# 30-FT4232_LEVEL_TRANSLATOR.net
KiCad netlist of a schematic drawn in Altium Designer
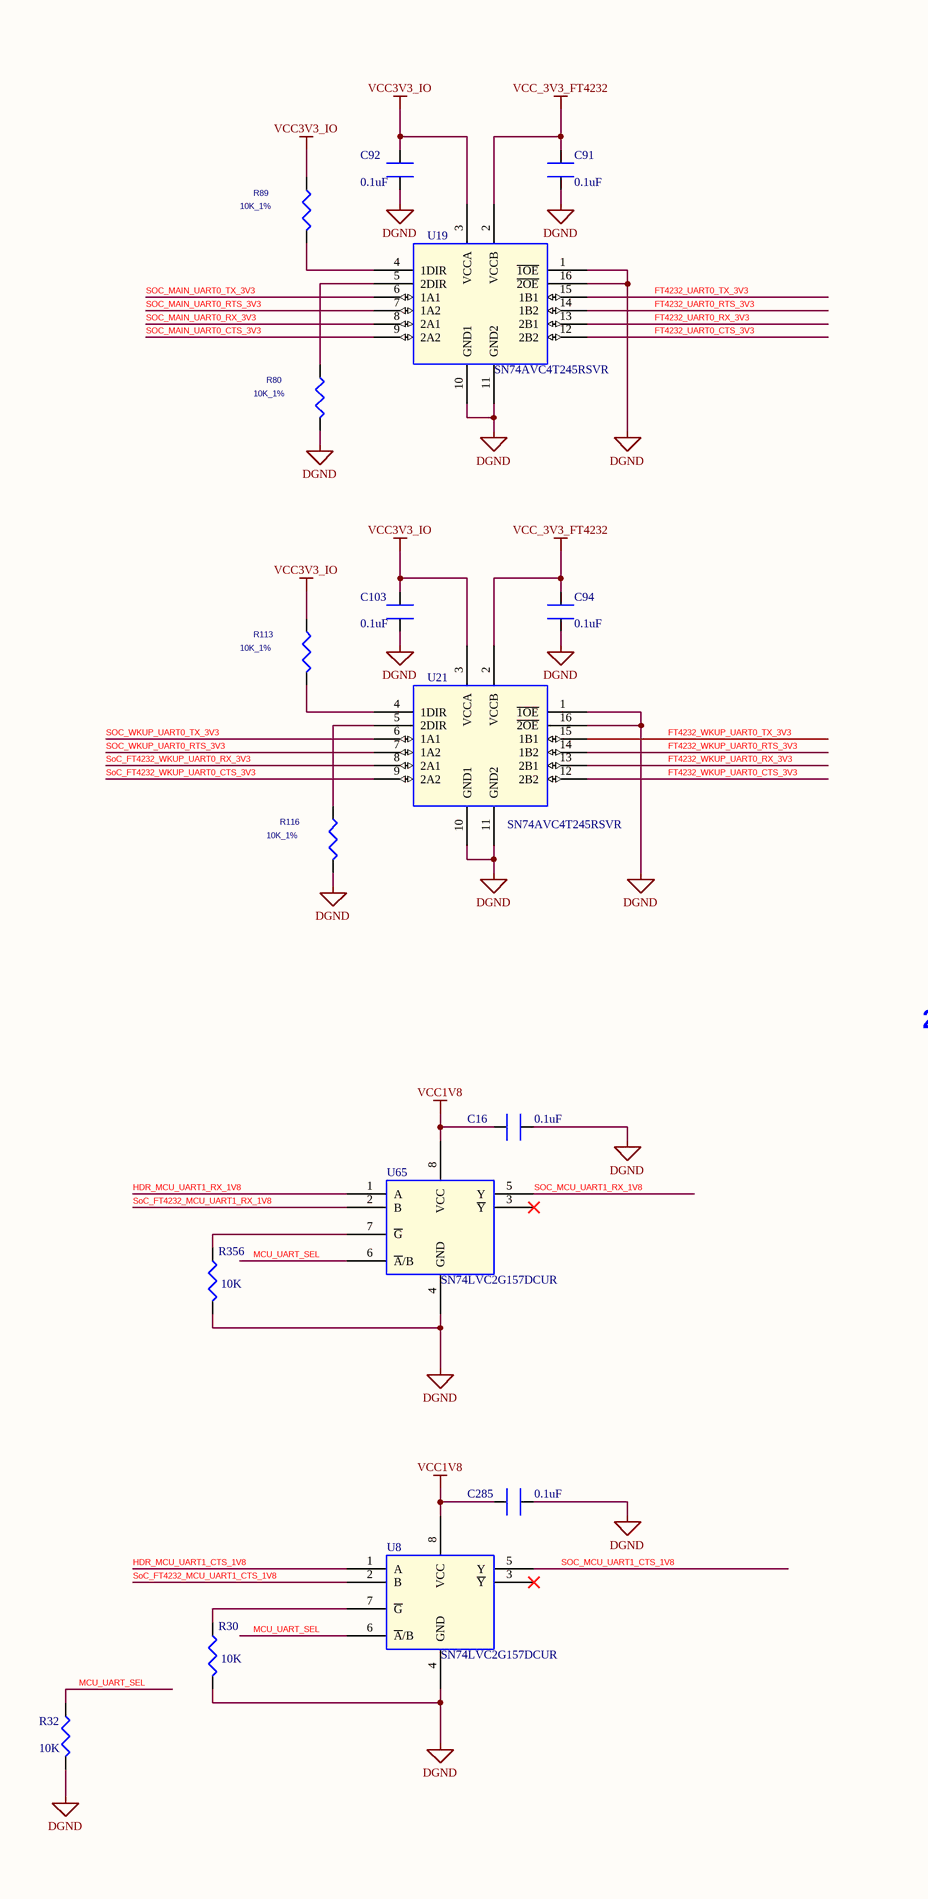
[diagram p0: 30-FT4232 LEVEL TRANSLATOR.SchDoc, left]
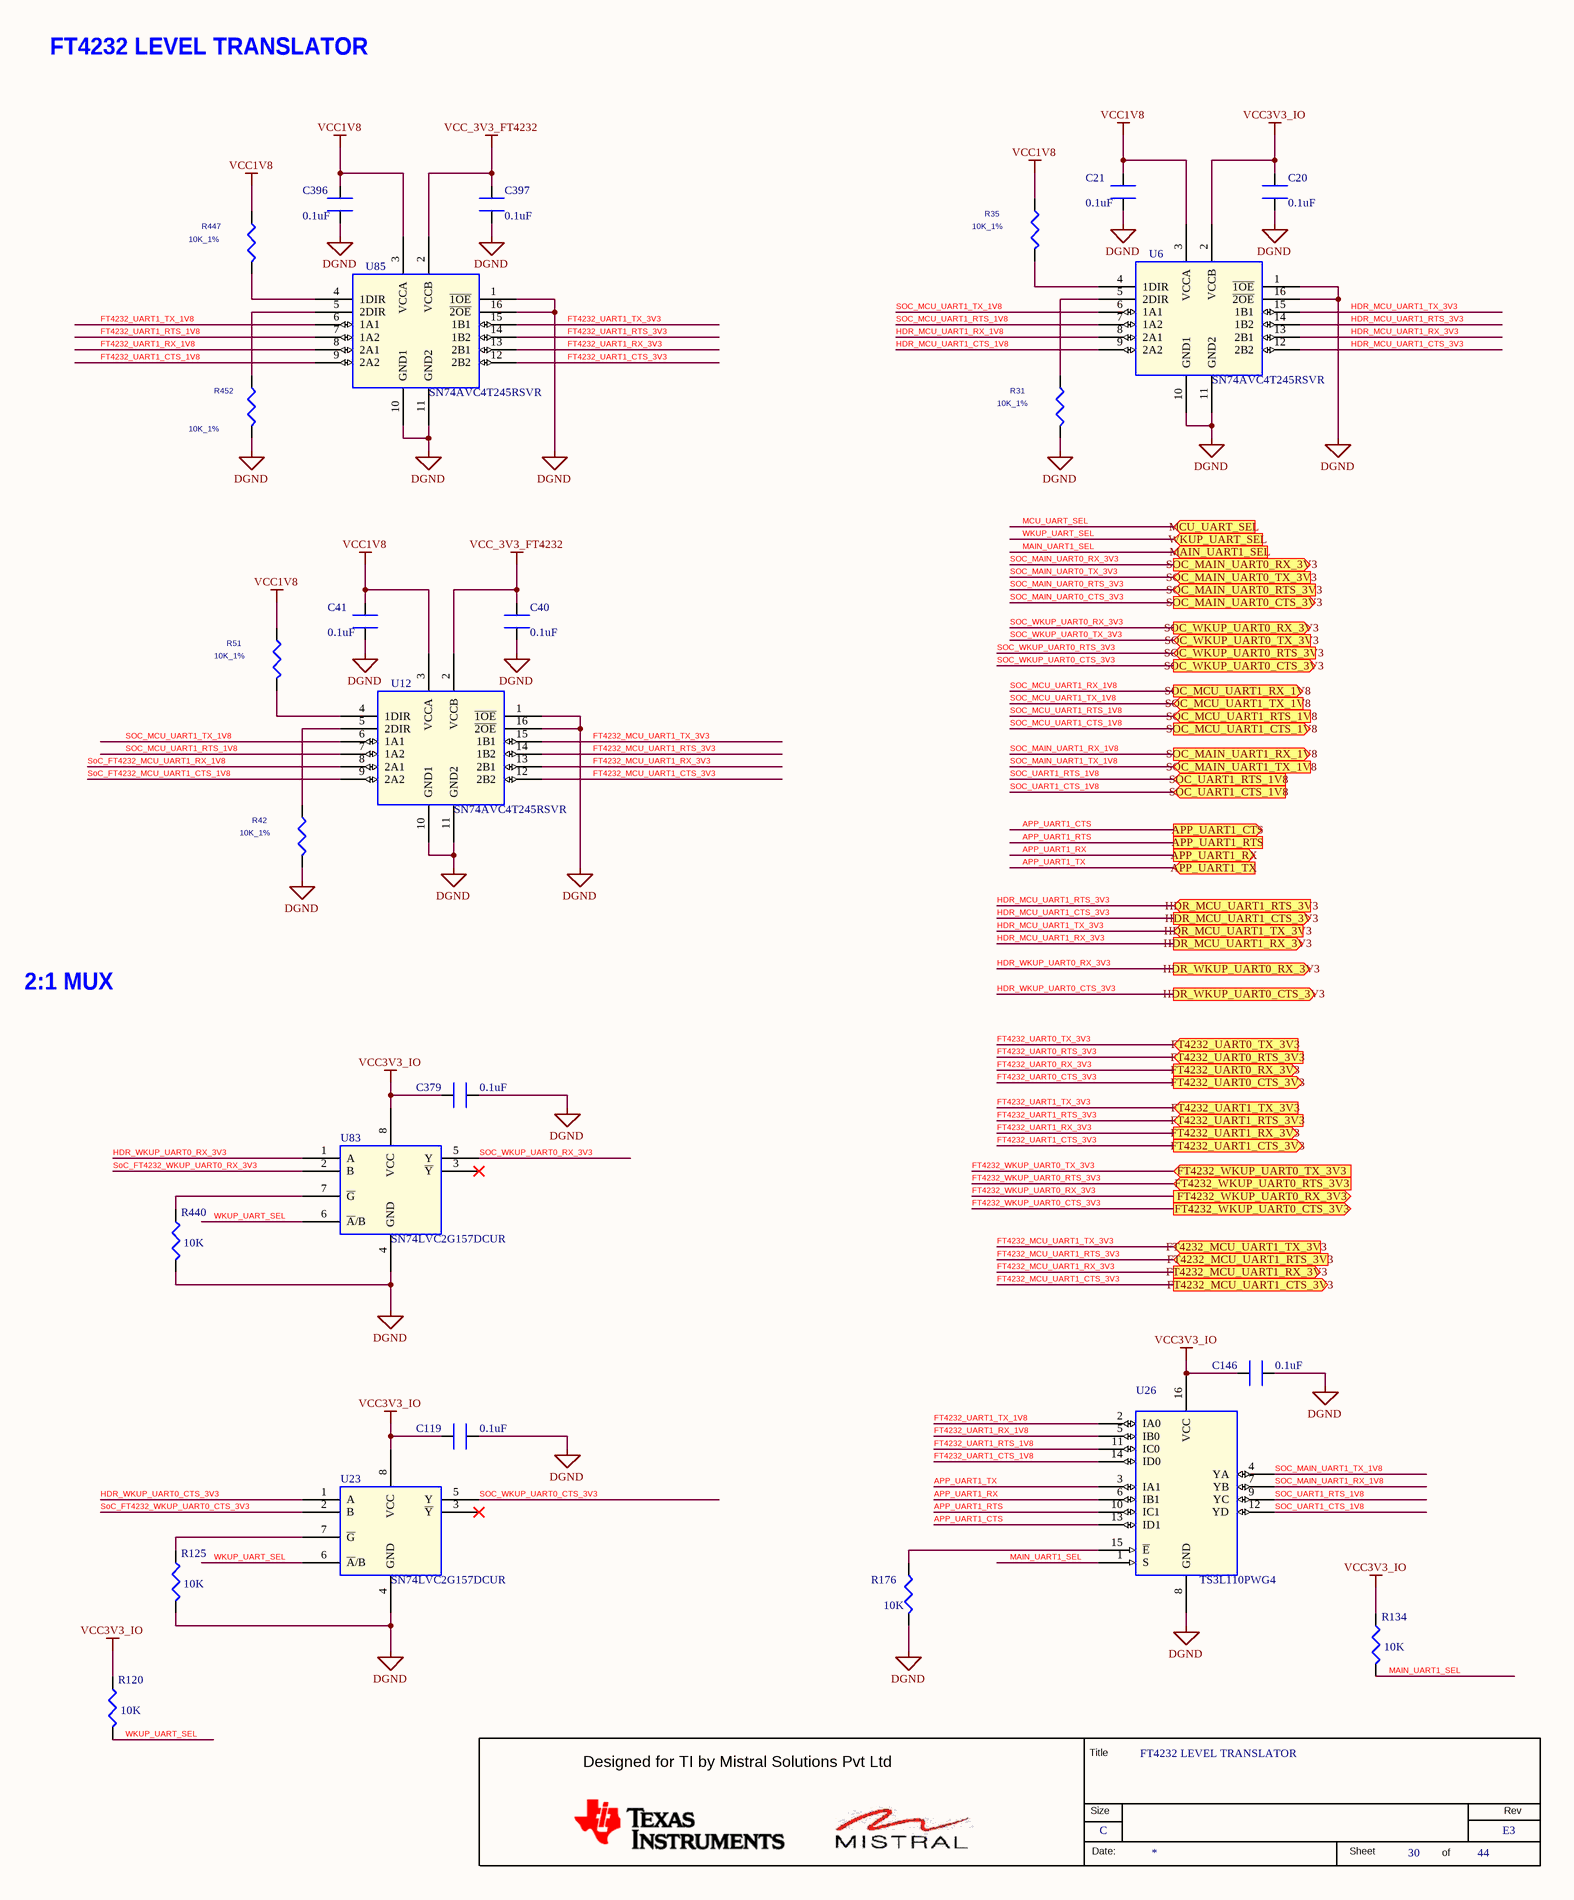
[diagram p1: 30-FT4232 LEVEL TRANSLATOR.SchDoc, right]

(export (version "E")
  (design (tool "Eeschema 10.0.6"))
  (components
    (comp (ref "C16")
      (value "0.1uF")
      (footprint "TMDX654GPEVM_BRD:CAP0201_0-5")
      (description "CAP CERAMIC 0.1uF 16V 10% X5R 0201")
      (fields
        (field (name "MISTRAL PART NO") "120009030072-R")
        (field (name "MFR_PART_NUMBER") "GRM033R61C104KE84J")
      )
      (libsource (lib "*") (part "CAP_Dup3"))
    )
    (comp (ref "C20")
      (value "0.1uF")
      (footprint "TMDX654GPEVM_BRD:CAP0201_0-5")
      (description "CAP CERAMIC 0.1uF 16V 10% X5R 0201")
      (fields (field (name "DISTRIBUTOR_PART_NUMBER") "490-16742-1-ND") (field (name "VOLTAGE") "16V"))
      (libsource (lib "*") (part "CAP_Dup3"))
    )
    (comp (ref "C21")
      (value "0.1uF")
      (footprint "TMDX654GPEVM_BRD:CAP0201_0-5")
      (description "CAP CERAMIC 0.1uF 16V 10% X5R 0201")
      (fields
        (field (name "MISTRAL PART NO") "120009030072-R")
        (field (name "MFR_PART_NUMBER") "GRM033R61C104KE84J")
      )
      (libsource (lib "*") (part "CAP_Dup3"))
    )
    (comp (ref "C40")
      (value "0.1uF")
      (footprint "TMDX654GPEVM_BRD:CAP0201_0-5")
      (description "CAP CERAMIC 0.1uF 16V 10% X5R 0201")
      (fields (field (name "DISTRIBUTOR_PART_NUMBER") "490-16742-1-ND") (field (name "VOLTAGE") "16V"))
      (libsource (lib "*") (part "CAP_Dup3"))
    )
    (comp (ref "C41")
      (value "0.1uF")
      (footprint "TMDX654GPEVM_BRD:CAP0201_0-5")
      (description "CAP CERAMIC 0.1uF 16V 10% X5R 0201")
      (fields
        (field (name "MISTRAL PART NO") "120009030072-R")
        (field (name "MFR_PART_NUMBER") "GRM033R61C104KE84J")
      )
      (libsource (lib "*") (part "CAP_Dup3"))
    )
    (comp (ref "C91")
      (value "0.1uF")
      (footprint "TMDX654GPEVM_BRD:CAP0201_0-5")
      (description "CAP CERAMIC 0.1uF 16V 10% X5R 0201")
      (fields
        (field (name "MISTRAL PART NO") "120009030072-R")
        (field (name "MFR_PART_NUMBER") "GRM033R61C104KE84J")
      )
      (libsource (lib "*") (part "CAP_Dup3"))
    )
    (comp (ref "C92")
      (value "0.1uF")
      (footprint "TMDX654GPEVM_BRD:CAP0201_0-5")
      (description "CAP CERAMIC 0.1uF 16V 10% X5R 0201")
      (fields (field (name "DISTRIBUTOR_PART_NUMBER") "490-16742-1-ND") (field (name "VOLTAGE") "16V"))
      (libsource (lib "*") (part "CAP_Dup3"))
    )
    (comp (ref "C94")
      (value "0.1uF")
      (footprint "TMDX654GPEVM_BRD:CAP0201_0-5")
      (description "CAP CERAMIC 0.1uF 16V 10% X5R 0201")
      (fields
        (field (name "MISTRAL PART NO") "120009030072-R")
        (field (name "MFR_PART_NUMBER") "GRM033R61C104KE84J")
      )
      (libsource (lib "*") (part "CAP_Dup3"))
    )
    (comp (ref "C103")
      (value "0.1uF")
      (footprint "TMDX654GPEVM_BRD:CAP0201_0-5")
      (description "CAP CERAMIC 0.1uF 16V 10% X5R 0201")
      (fields (field (name "DISTRIBUTOR_PART_NUMBER") "490-16742-1-ND") (field (name "VOLTAGE") "16V"))
      (libsource (lib "*") (part "CAP_Dup3"))
    )
    (comp (ref "C119")
      (value "0.1uF")
      (footprint "TMDX654GPEVM_BRD:CAP0201_0-5")
      (description "CAP CERAMIC 0.1uF 16V 10% X5R 0201")
      (fields (field (name "DISTRIBUTOR_PART_NUMBER") "490-16742-1-ND") (field (name "VOLTAGE") "16V"))
      (libsource (lib "*") (part "CAP_Dup3"))
    )
    (comp (ref "C146")
      (value "0.1uF")
      (footprint "TMDX654GPEVM_BRD:CAP0201_0-5")
      (description "CAP CERAMIC 0.1uF 16V 10% X5R 0201")
      (fields
        (field (name "MISTRAL PART NO") "120009030072-R")
        (field (name "MFR_PART_NUMBER") "GRM033R61C104KE84J")
      )
      (libsource (lib "*") (part "CAP_Dup3"))
    )
    (comp (ref "C285")
      (value "0.1uF")
      (footprint "TMDX654GPEVM_BRD:CAP0201_0-5")
      (description "CAP CERAMIC 0.1uF 16V 10% X5R 0201")
      (fields (field (name "DISTRIBUTOR_PART_NUMBER") "490-16742-1-ND") (field (name "VOLTAGE") "16V"))
      (libsource (lib "*") (part "CAP_Dup3"))
    )
    (comp (ref "C379")
      (value "0.1uF")
      (footprint "TMDX654GPEVM_BRD:CAP0201_0-5")
      (description "CAP CERAMIC 0.1uF 16V 10% X5R 0201")
      (fields
        (field (name "MISTRAL PART NO") "120009030072-R")
        (field (name "MFR_PART_NUMBER") "GRM033R61C104KE84J")
      )
      (libsource (lib "*") (part "CAP_Dup3"))
    )
    (comp (ref "C396")
      (value "0.1uF")
      (footprint "TMDX654GPEVM_BRD:CAP0201_0-5")
      (description "CAP CERAMIC 0.1uF 16V 10% X5R 0201")
      (fields (field (name "DISTRIBUTOR_PART_NUMBER") "490-16742-1-ND") (field (name "VOLTAGE") "16V"))
      (libsource (lib "*") (part "CAP_Dup3"))
    )
    (comp (ref "C397")
      (value "0.1uF")
      (footprint "TMDX654GPEVM_BRD:CAP0201_0-5")
      (description "CAP CERAMIC 0.1uF 16V 10% X5R 0201")
      (fields
        (field (name "MISTRAL PART NO") "120009030072-R")
        (field (name "MFR_PART_NUMBER") "GRM033R61C104KE84J")
      )
      (libsource (lib "*") (part "CAP_Dup3"))
    )
    (comp (ref "R30")
      (value "10K")
      (footprint "RES0402_0-5")
      (description "RES 10K 1/16W 5% 0402")
      (fields
        (field (name "MISTRAL PART NO") "110009030208-R")
        (field (name "MFR_PART_NUMBER") "RC0402JR-0710KL")
      )
      (libsource (lib "*") (part "RESISTOR_Dup5"))
    )
    (comp (ref "R31")
      (value "10K_1%")
      (footprint "RES0402_0-5")
      (description "RES 10K 1/16W 1% 0402")
      (fields (field (name "DISTRIBUTOR_PART_NUMBER") "311-10.0KLRTR-ND") (field (name "TOLERANCE") "1%"))
      (libsource (lib "*") (part "RESISTOR_Dup2"))
    )
    (comp (ref "R32")
      (value "10K")
      (footprint "RES0402_0-5")
      (description "RES 10K 1/16W 5% 0402")
      (fields
        (field (name "MISTRAL PART NO") "110009030208-R")
        (field (name "MFR_PART_NUMBER") "RC0402JR-0710KL")
      )
      (libsource (lib "*") (part "RESISTOR_Dup5"))
    )
    (comp (ref "R35")
      (value "10K_1%")
      (footprint "RES0402_0-5")
      (description "RES 10K 1/16W 1% 0402")
      (fields (field (name "DISTRIBUTOR_PART_NUMBER") "311-10.0KLRTR-ND") (field (name "TOLERANCE") "1%"))
      (libsource (lib "*") (part "RESISTOR_Dup2"))
    )
    (comp (ref "R42")
      (value "10K_1%")
      (footprint "RES0402_0-5")
      (description "RES 10K 1/16W 1% 0402")
      (fields (field (name "VOLTAGE") "NA") (field (name "DISTRIBUTOR_PART_NUMBER") "311-10.0KLRTR-ND"))
      (libsource (lib "*") (part "RESISTOR_Dup2"))
    )
    (comp (ref "R51")
      (value "10K_1%")
      (footprint "RES0402_0-5")
      (description "RES 10K 1/16W 1% 0402")
      (fields (field (name "VOLTAGE") "NA") (field (name "DISTRIBUTOR_PART_NUMBER") "311-10.0KLRTR-ND"))
      (libsource (lib "*") (part "RESISTOR_Dup2"))
    )
    (comp (ref "R80")
      (value "10K_1%")
      (footprint "RES0402_0-5")
      (description "RES 10K 1/16W 1% 0402")
      (fields (field (name "VOLTAGE") "NA") (field (name "DISTRIBUTOR_PART_NUMBER") "311-10.0KLRTR-ND"))
      (libsource (lib "*") (part "RESISTOR_Dup2"))
    )
    (comp (ref "R89")
      (value "10K_1%")
      (footprint "RES0402_0-5")
      (description "RES 10K 1/16W 1% 0402")
      (fields (field (name "VOLTAGE") "NA") (field (name "MISTRAL PART NO") "110009030220-P"))
      (libsource (lib "*") (part "RESISTOR_Dup2"))
    )
    (comp (ref "R113")
      (value "10K_1%")
      (footprint "RES0402_0-5")
      (description "RES 10K 1/16W 1% 0402")
      (fields (field (name "VOLTAGE") "NA") (field (name "MISTRAL PART NO") "110009030220-P"))
      (libsource (lib "*") (part "RESISTOR_Dup2"))
    )
    (comp (ref "R116")
      (value "10K_1%")
      (footprint "RES0402_0-5")
      (description "RES 10K 1/16W 1% 0402")
      (fields (field (name "VOLTAGE") "NA") (field (name "MISTRAL PART NO") "110009030220-P"))
      (libsource (lib "*") (part "RESISTOR_Dup2"))
    )
    (comp (ref "R120")
      (value "10K")
      (footprint "RES0402_0-5")
      (description "RES 10K 1/16W 5% 0402")
      (fields (field (name "DISTRIBUTOR_PART_NUMBER") "311-10KJRCT-ND") (field (name "VOLTAGE") "NA"))
      (libsource (lib "*") (part "RESISTOR_Dup5"))
    )
    (comp (ref "R125")
      (value "10K")
      (footprint "RES0402_0-5")
      (description "RES 10K 1/16W 5% 0402")
      (fields
        (field (name "MISTRAL PART NO") "110009030208-R")
        (field (name "MFR_PART_NUMBER") "RC0402JR-0710KL")
      )
      (libsource (lib "*") (part "RESISTOR_Dup5"))
    )
    (comp (ref "R134")
      (value "10K")
      (footprint "RES0402_0-5")
      (description "RES 10K 1/16W 5% 0402")
      (fields
        (field (name "MISTRAL PART NO") "110009030208-R")
        (field (name "MFR_PART_NUMBER") "RC0402JR-0710KL")
      )
      (libsource (lib "*") (part "RESISTOR_Dup5"))
    )
    (comp (ref "R176")
      (value "10K")
      (footprint "RES0402_0-5")
      (description "RES 10K 1/16W 5% 0402")
      (fields (field (name "DISTRIBUTOR_PART_NUMBER") "311-10KJRCT-ND") (field (name "VOLTAGE") "NA"))
      (libsource (lib "*") (part "RESISTOR_Dup5"))
    )
    (comp (ref "R356")
      (value "10K")
      (footprint "RES0402_0-5")
      (description "RES 10K 1/16W 5% 0402")
      (fields (field (name "DISTRIBUTOR_PART_NUMBER") "311-10KJRCT-ND") (field (name "VOLTAGE") "NA"))
      (libsource (lib "*") (part "RESISTOR_Dup5"))
    )
    (comp (ref "R440")
      (value "10K")
      (footprint "RES0402_0-5")
      (description "RES 10K 1/16W 5% 0402")
      (fields (field (name "DISTRIBUTOR_PART_NUMBER") "311-10KJRCT-ND") (field (name "VOLTAGE") "NA"))
      (libsource (lib "*") (part "RESISTOR_Dup5"))
    )
    (comp (ref "R447")
      (value "10K_1%")
      (footprint "RES0402_0-5")
      (description "RES 10K 1/16W 1% 0402")
      (fields (field (name "VOLTAGE") "NA") (field (name "MISTRAL PART NO") "110009030220-P"))
      (libsource (lib "*") (part "RESISTOR_Dup2"))
    )
    (comp (ref "R452")
      (value "10K_1%")
      (footprint "RES0402_0-5")
      (description "RES 10K 1/16W 1% 0402")
      (fields (field (name "DISTRIBUTOR_PART_NUMBER") "311-10.0KLRTR-ND") (field (name "TOLERANCE") "1%"))
      (libsource (lib "*") (part "RESISTOR_Dup2"))
    )
    (comp (ref "U6")
      (value "SN74AVC4T245RSVR")
      (footprint "UQFN16_15-74_105X75_0-6")
      (description "IC BUS TRANSCEIVER 4-BIT DUAL SUPPLY QFN16")
      (fields (field (name "MISTRAL PART NO") "141011040011-R") (field (name "TOLERANCE") "NA"))
      (libsource (lib "*") (part "SN74AVC4T245RSV_UQFN16"))
    )
    (comp (ref "U8")
      (value "SN74LVC2G157DCUR")
      (footprint "VSSOP8_19-68_85X95_0-9")
      (description "IC 2-LINE TO 1-LINE DATA SELECTOR MULTIPLEXER VSSOP8")
      (fields (field (name "DISTRIBUTOR_PART_NUMBER") "296-12605-1-ND") (field (name "VOLTAGE") "NA"))
      (libsource (lib "*") (part "SN74LVC2G157DCUR_VSSOP8"))
    )
    (comp (ref "U12")
      (value "SN74AVC4T245RSVR")
      (footprint "UQFN16_15-74_105X75_0-6")
      (description "IC BUS TRANSCEIVER 4-BIT DUAL SUPPLY QFN16")
      (fields (field (name "MISTRAL PART NO") "141011040011-R") (field (name "TOLERANCE") "NA"))
      (libsource (lib "*") (part "SN74AVC4T245RSV_UQFN16"))
    )
    (comp (ref "U19")
      (value "SN74AVC4T245RSVR")
      (footprint "UQFN16_15-74_105X75_0-6")
      (description "IC BUS TRANSCEIVER 4-BIT DUAL SUPPLY QFN16")
      (fields (field (name "DISTRIBUTOR_PART_NUMBER") "296-24366-1-ND") (field (name "VOLTAGE") "NA"))
      (libsource (lib "*") (part "SN74AVC4T245RSV_UQFN16"))
    )
    (comp (ref "U21")
      (value "SN74AVC4T245RSVR")
      (footprint "UQFN16_15-74_105X75_0-6")
      (description "IC BUS TRANSCEIVER 4-BIT DUAL SUPPLY QFN16")
      (fields (field (name "MISTRAL PART NO") "141011040011-R") (field (name "TOLERANCE") "NA"))
      (libsource (lib "*") (part "SN74AVC4T245RSV_UQFN16"))
    )
    (comp (ref "U23")
      (value "SN74LVC2G157DCUR")
      (footprint "VSSOP8_19-68_85X95_0-9")
      (description "IC 2-LINE TO 1-LINE DATA SELECTOR MULTIPLEXER VSSOP8")
      (fields (field (name "MISTRAL PART NO") "141017090014-R") (field (name "TOLERANCE") "NA"))
      (libsource (lib "*") (part "SN74LVC2G157DCUR_VSSOP8"))
    )
    (comp (ref "U26")
      (value "TS3L110PWG4")
      (footprint "TSSOP16_25-59_205X180")
      (description "IC QUAD SPDT SWITCH 8-4 CHANNEL MULTIPLEXER/DEMULTIPLEXER TSSOP16")
      (fields (field (name "MISTRAL PART NO") "140114110002-R") (field (name "TOLERANCE") "NA"))
      (libsource (lib "*") (part "TS3L110PWG4_TSSOP16"))
    )
    (comp (ref "U65")
      (value "SN74LVC2G157DCUR")
      (footprint "VSSOP8_19-68_85X95_0-9")
      (description "IC 2-LINE TO 1-LINE DATA SELECTOR MULTIPLEXER VSSOP8")
      (fields (field (name "MISTRAL PART NO") "141017090014-R") (field (name "TOLERANCE") "NA"))
      (libsource (lib "*") (part "SN74LVC2G157DCUR_VSSOP8"))
    )
    (comp (ref "U83")
      (value "SN74LVC2G157DCUR")
      (footprint "VSSOP8_19-68_85X95_0-9")
      (description "IC 2-LINE TO 1-LINE DATA SELECTOR MULTIPLEXER VSSOP8")
      (fields (field (name "DISTRIBUTOR_PART_NUMBER") "296-12605-1-ND") (field (name "VOLTAGE") "NA"))
      (libsource (lib "*") (part "SN74LVC2G157DCUR_VSSOP8"))
    )
    (comp (ref "U85")
      (value "SN74AVC4T245RSVR")
      (footprint "UQFN16_15-74_105X75_0-6")
      (description "IC BUS TRANSCEIVER 4-BIT DUAL SUPPLY QFN16")
      (fields (field (name "DISTRIBUTOR_PART_NUMBER") "296-24366-1-ND") (field (name "VOLTAGE") "NA"))
      (libsource (lib "*") (part "SN74AVC4T245RSV_UQFN16"))
    )
  )
  (nets
    (net (code "1") (name "/APP_UART1_CTS") (class "Default")
      (node (ref "U26") (pin "13") (pinfunction "ID1_13") (pintype "bidirectional"))
    )
    (net (code "2") (name "/APP_UART1_RTS") (class "Default")
      (node (ref "U26") (pin "10") (pinfunction "IC1_10") (pintype "bidirectional"))
    )
    (net (code "3") (name "/APP_UART1_RX") (class "Default")
      (node (ref "U26") (pin "6") (pinfunction "IB1_6") (pintype "bidirectional"))
    )
    (net (code "4") (name "/APP_UART1_TX") (class "Default")
      (node (ref "U26") (pin "3") (pinfunction "IA1_3") (pintype "bidirectional"))
    )
    (net (code "5") (name "/FT4232_MCU_UART1_CTS_3V3") (class "Default")
      (node (ref "U12") (pin "12") (pinfunction "2B2_12") (pintype "bidirectional"))
    )
    (net (code "6") (name "/FT4232_MCU_UART1_RTS_3V3") (class "Default")
      (node (ref "U12") (pin "14") (pinfunction "1B2_14") (pintype "bidirectional"))
    )
    (net (code "7") (name "/FT4232_MCU_UART1_RX_3V3") (class "Default")
      (node (ref "U12") (pin "13") (pinfunction "2B1_13") (pintype "bidirectional"))
    )
    (net (code "8") (name "/FT4232_MCU_UART1_TX_3V3") (class "Default")
      (node (ref "U12") (pin "15") (pinfunction "1B1_15") (pintype "bidirectional"))
    )
    (net (code "9") (name "/FT4232_UART0_CTS_3V3") (class "Default")
      (node (ref "U19") (pin "12") (pinfunction "2B2_12") (pintype "bidirectional"))
    )
    (net (code "10") (name "/FT4232_UART0_RTS_3V3") (class "Default")
      (node (ref "U19") (pin "14") (pinfunction "1B2_14") (pintype "bidirectional"))
    )
    (net (code "11") (name "/FT4232_UART0_RX_3V3") (class "Default")
      (node (ref "U19") (pin "13") (pinfunction "2B1_13") (pintype "bidirectional"))
    )
    (net (code "12") (name "/FT4232_UART0_TX_3V3") (class "Default")
      (node (ref "U19") (pin "15") (pinfunction "1B1_15") (pintype "bidirectional"))
    )
    (net (code "13") (name "/FT4232_UART1_CTS_1V8") (class "Default")
      (node (ref "U26") (pin "14") (pinfunction "ID0_14") (pintype "bidirectional"))
      (node (ref "U85") (pin "9") (pinfunction "2A2_9") (pintype "bidirectional"))
    )
    (net (code "14") (name "/FT4232_UART1_CTS_3V3") (class "Default")
      (node (ref "U85") (pin "12") (pinfunction "2B2_12") (pintype "bidirectional"))
    )
    (net (code "15") (name "/FT4232_UART1_RTS_1V8") (class "Default")
      (node (ref "U26") (pin "11") (pinfunction "IC0_11") (pintype "bidirectional"))
      (node (ref "U85") (pin "7") (pinfunction "1A2_7") (pintype "bidirectional"))
    )
    (net (code "16") (name "/FT4232_UART1_RTS_3V3") (class "Default")
      (node (ref "U85") (pin "14") (pinfunction "1B2_14") (pintype "bidirectional"))
    )
    (net (code "17") (name "/FT4232_UART1_RX_1V8") (class "Default")
      (node (ref "U26") (pin "5") (pinfunction "IB0_5") (pintype "bidirectional"))
      (node (ref "U85") (pin "8") (pinfunction "2A1_8") (pintype "bidirectional"))
    )
    (net (code "18") (name "/FT4232_UART1_RX_3V3") (class "Default")
      (node (ref "U85") (pin "13") (pinfunction "2B1_13") (pintype "bidirectional"))
    )
    (net (code "19") (name "/FT4232_UART1_TX_1V8") (class "Default")
      (node (ref "U26") (pin "2") (pinfunction "IA0_2") (pintype "bidirectional"))
      (node (ref "U85") (pin "6") (pinfunction "1A1_6") (pintype "bidirectional"))
    )
    (net (code "20") (name "/FT4232_UART1_TX_3V3") (class "Default")
      (node (ref "U85") (pin "15") (pinfunction "1B1_15") (pintype "bidirectional"))
    )
    (net (code "21") (name "/FT4232_WKUP_UART0_CTS_3V3") (class "Default")
      (node (ref "U21") (pin "12") (pinfunction "2B2_12") (pintype "bidirectional"))
    )
    (net (code "22") (name "/FT4232_WKUP_UART0_RTS_3V3") (class "Default")
      (node (ref "U21") (pin "14") (pinfunction "1B2_14") (pintype "bidirectional"))
    )
    (net (code "23") (name "/FT4232_WKUP_UART0_RX_3V3") (class "Default")
      (node (ref "U21") (pin "13") (pinfunction "2B1_13") (pintype "bidirectional"))
    )
    (net (code "24") (name "/FT4232_WKUP_UART0_TX_3V3") (class "Default")
      (node (ref "U21") (pin "15") (pinfunction "1B1_15") (pintype "bidirectional"))
    )
    (net (code "25") (name "/HDR_MCU_UART1_CTS_1V8") (class "Default")
      (node (ref "U6") (pin "9") (pinfunction "2A2_9") (pintype "bidirectional"))
      (node (ref "U8") (pin "1") (pinfunction "A_1") (pintype "passive"))
    )
    (net (code "26") (name "/HDR_MCU_UART1_CTS_3V3") (class "Default")
      (node (ref "U6") (pin "12") (pinfunction "2B2_12") (pintype "bidirectional"))
    )
    (net (code "27") (name "/HDR_MCU_UART1_RTS_3V3") (class "Default")
      (node (ref "U6") (pin "14") (pinfunction "1B2_14") (pintype "bidirectional"))
    )
    (net (code "28") (name "/HDR_MCU_UART1_RX_1V8") (class "Default")
      (node (ref "U6") (pin "8") (pinfunction "2A1_8") (pintype "bidirectional"))
      (node (ref "U65") (pin "1") (pinfunction "A_1") (pintype "passive"))
    )
    (net (code "29") (name "/HDR_MCU_UART1_RX_3V3") (class "Default")
      (node (ref "U6") (pin "13") (pinfunction "2B1_13") (pintype "bidirectional"))
    )
    (net (code "30") (name "/HDR_MCU_UART1_TX_3V3") (class "Default")
      (node (ref "U6") (pin "15") (pinfunction "1B1_15") (pintype "bidirectional"))
    )
    (net (code "31") (name "/HDR_WKUP_UART0_CTS_3V3") (class "Default")
      (node (ref "U23") (pin "1") (pinfunction "A_1") (pintype "passive"))
    )
    (net (code "32") (name "/HDR_WKUP_UART0_RX_3V3") (class "Default")
      (node (ref "U83") (pin "1") (pinfunction "A_1") (pintype "passive"))
    )
    (net (code "33") (name "/MAIN_UART1_SEL") (class "Default")
      (node (ref "R134") (pin "2") (pinfunction "2_2") (pintype "passive"))
      (node (ref "U26") (pin "1") (pinfunction "S_1") (pintype "input"))
    )
    (net (code "34") (name "/MCU_UART_SEL") (class "Default")
      (node (ref "R32") (pin "1") (pinfunction "1_1") (pintype "passive"))
      (node (ref "U65") (pin "6") (pinfunction "~{A}/B_6") (pintype "passive"))
      (node (ref "U8") (pin "6") (pinfunction "~{A}/B_6") (pintype "passive"))
    )
    (net (code "35") (name "/SOC_MAIN_UART0_CTS_3V3") (class "Default")
      (node (ref "U19") (pin "9") (pinfunction "2A2_9") (pintype "bidirectional"))
    )
    (net (code "36") (name "/SOC_MAIN_UART0_RTS_3V3") (class "Default")
      (node (ref "U19") (pin "7") (pinfunction "1A2_7") (pintype "bidirectional"))
    )
    (net (code "37") (name "/SOC_MAIN_UART0_RX_3V3") (class "Default")
      (node (ref "U19") (pin "8") (pinfunction "2A1_8") (pintype "bidirectional"))
    )
    (net (code "38") (name "/SOC_MAIN_UART0_TX_3V3") (class "Default")
      (node (ref "U19") (pin "6") (pinfunction "1A1_6") (pintype "bidirectional"))
    )
    (net (code "39") (name "/SOC_MAIN_UART1_RX_1V8") (class "Default")
      (node (ref "U26") (pin "7") (pinfunction "YB_7") (pintype "bidirectional"))
    )
    (net (code "40") (name "/SOC_MAIN_UART1_TX_1V8") (class "Default")
      (node (ref "U26") (pin "4") (pinfunction "YA_4") (pintype "bidirectional"))
    )
    (net (code "41") (name "/SOC_MCU_UART1_CTS_1V8") (class "Default")
      (node (ref "U8") (pin "5") (pinfunction "Y_5") (pintype "passive"))
    )
    (net (code "42") (name "/SOC_MCU_UART1_RTS_1V8") (class "Default")
      (node (ref "U12") (pin "7") (pinfunction "1A2_7") (pintype "bidirectional"))
      (node (ref "U6") (pin "7") (pinfunction "1A2_7") (pintype "bidirectional"))
    )
    (net (code "43") (name "/SOC_MCU_UART1_RX_1V8") (class "Default")
      (node (ref "U65") (pin "5") (pinfunction "Y_5") (pintype "passive"))
    )
    (net (code "44") (name "/SOC_MCU_UART1_TX_1V8") (class "Default")
      (node (ref "U12") (pin "6") (pinfunction "1A1_6") (pintype "bidirectional"))
      (node (ref "U6") (pin "6") (pinfunction "1A1_6") (pintype "bidirectional"))
    )
    (net (code "45") (name "/SOC_UART1_CTS_1V8") (class "Default")
      (node (ref "U26") (pin "12") (pinfunction "YD_12") (pintype "bidirectional"))
    )
    (net (code "46") (name "/SOC_UART1_RTS_1V8") (class "Default")
      (node (ref "U26") (pin "9") (pinfunction "YC_9") (pintype "bidirectional"))
    )
    (net (code "47") (name "/SOC_WKUP_UART0_CTS_3V3") (class "Default")
      (node (ref "U23") (pin "5") (pinfunction "Y_5") (pintype "passive"))
    )
    (net (code "48") (name "/SOC_WKUP_UART0_RTS_3V3") (class "Default")
      (node (ref "U21") (pin "7") (pinfunction "1A2_7") (pintype "bidirectional"))
    )
    (net (code "49") (name "/SOC_WKUP_UART0_RX_3V3") (class "Default")
      (node (ref "U83") (pin "5") (pinfunction "Y_5") (pintype "passive"))
    )
    (net (code "50") (name "/SOC_WKUP_UART0_TX_3V3") (class "Default")
      (node (ref "U21") (pin "6") (pinfunction "1A1_6") (pintype "bidirectional"))
    )
    (net (code "51") (name "/SoC_FT4232_MCU_UART1_CTS_1V8") (class "Default")
      (node (ref "U12") (pin "9") (pinfunction "2A2_9") (pintype "bidirectional"))
      (node (ref "U8") (pin "2") (pinfunction "B_2") (pintype "passive"))
    )
    (net (code "52") (name "/SoC_FT4232_MCU_UART1_RX_1V8") (class "Default")
      (node (ref "U12") (pin "8") (pinfunction "2A1_8") (pintype "bidirectional"))
      (node (ref "U65") (pin "2") (pinfunction "B_2") (pintype "passive"))
    )
    (net (code "53") (name "/SoC_FT4232_WKUP_UART0_CTS_3V3") (class "Default")
      (node (ref "U21") (pin "9") (pinfunction "2A2_9") (pintype "bidirectional"))
      (node (ref "U23") (pin "2") (pinfunction "B_2") (pintype "passive"))
    )
    (net (code "54") (name "/SoC_FT4232_WKUP_UART0_RX_3V3") (class "Default")
      (node (ref "U21") (pin "8") (pinfunction "2A1_8") (pintype "bidirectional"))
      (node (ref "U83") (pin "2") (pinfunction "B_2") (pintype "passive"))
    )
    (net (code "55") (name "/WKUP_UART_SEL") (class "Default")
      (node (ref "R120") (pin "2") (pinfunction "2_2") (pintype "passive"))
      (node (ref "U23") (pin "6") (pinfunction "~{A}/B_6") (pintype "passive"))
      (node (ref "U83") (pin "6") (pinfunction "~{A}/B_6") (pintype "passive"))
    )
    (net (code "56") (name "DGND") (class "Default")
      (node (ref "C103") (pin "2") (pinfunction "2_2") (pintype "passive"))
      (node (ref "C119") (pin "2") (pinfunction "2_2") (pintype "passive"))
      (node (ref "C146") (pin "2") (pinfunction "2_2") (pintype "passive"))
      (node (ref "C16") (pin "2") (pinfunction "2_2") (pintype "passive"))
      (node (ref "C20") (pin "2") (pinfunction "2_2") (pintype "passive"))
      (node (ref "C21") (pin "2") (pinfunction "2_2") (pintype "passive"))
      (node (ref "C285") (pin "2") (pinfunction "2_2") (pintype "passive"))
      (node (ref "C379") (pin "2") (pinfunction "2_2") (pintype "passive"))
      (node (ref "C396") (pin "2") (pinfunction "2_2") (pintype "passive"))
      (node (ref "C397") (pin "2") (pinfunction "2_2") (pintype "passive"))
      (node (ref "C40") (pin "2") (pinfunction "2_2") (pintype "passive"))
      (node (ref "C41") (pin "2") (pinfunction "2_2") (pintype "passive"))
      (node (ref "C91") (pin "2") (pinfunction "2_2") (pintype "passive"))
      (node (ref "C92") (pin "2") (pinfunction "2_2") (pintype "passive"))
      (node (ref "C94") (pin "2") (pinfunction "2_2") (pintype "passive"))
      (node (ref "R116") (pin "1") (pinfunction "1_1") (pintype "passive"))
      (node (ref "R125") (pin "2") (pinfunction "2_2") (pintype "passive"))
      (node (ref "R176") (pin "2") (pinfunction "2_2") (pintype "passive"))
      (node (ref "R30") (pin "2") (pinfunction "2_2") (pintype "passive"))
      (node (ref "R31") (pin "1") (pinfunction "1_1") (pintype "passive"))
      (node (ref "R32") (pin "2") (pinfunction "2_2") (pintype "passive"))
      (node (ref "R356") (pin "2") (pinfunction "2_2") (pintype "passive"))
      (node (ref "R42") (pin "1") (pinfunction "1_1") (pintype "passive"))
      (node (ref "R440") (pin "2") (pinfunction "2_2") (pintype "passive"))
      (node (ref "R452") (pin "1") (pinfunction "1_1") (pintype "passive"))
      (node (ref "R80") (pin "1") (pinfunction "1_1") (pintype "passive"))
      (node (ref "U12") (pin "1") (pinfunction "~{1OE}_1") (pintype "passive"))
      (node (ref "U12") (pin "10") (pinfunction "GND1_10") (pintype "power_in"))
      (node (ref "U12") (pin "11") (pinfunction "GND2_11") (pintype "power_in"))
      (node (ref "U12") (pin "16") (pinfunction "~{2OE}_16") (pintype "passive"))
      (node (ref "U19") (pin "1") (pinfunction "~{1OE}_1") (pintype "passive"))
      (node (ref "U19") (pin "10") (pinfunction "GND1_10") (pintype "power_in"))
      (node (ref "U19") (pin "11") (pinfunction "GND2_11") (pintype "power_in"))
      (node (ref "U19") (pin "16") (pinfunction "~{2OE}_16") (pintype "passive"))
      (node (ref "U21") (pin "1") (pinfunction "~{1OE}_1") (pintype "passive"))
      (node (ref "U21") (pin "10") (pinfunction "GND1_10") (pintype "power_in"))
      (node (ref "U21") (pin "11") (pinfunction "GND2_11") (pintype "power_in"))
      (node (ref "U21") (pin "16") (pinfunction "~{2OE}_16") (pintype "passive"))
      (node (ref "U23") (pin "4") (pinfunction "GND_4") (pintype "power_in"))
      (node (ref "U26") (pin "8") (pinfunction "GND_8") (pintype "power_in"))
      (node (ref "U6") (pin "1") (pinfunction "~{1OE}_1") (pintype "passive"))
      (node (ref "U6") (pin "10") (pinfunction "GND1_10") (pintype "power_in"))
      (node (ref "U6") (pin "11") (pinfunction "GND2_11") (pintype "power_in"))
      (node (ref "U6") (pin "16") (pinfunction "~{2OE}_16") (pintype "passive"))
      (node (ref "U65") (pin "4") (pinfunction "GND_4") (pintype "power_in"))
      (node (ref "U8") (pin "4") (pinfunction "GND_4") (pintype "power_in"))
      (node (ref "U83") (pin "4") (pinfunction "GND_4") (pintype "power_in"))
      (node (ref "U85") (pin "1") (pinfunction "~{1OE}_1") (pintype "passive"))
      (node (ref "U85") (pin "10") (pinfunction "GND1_10") (pintype "power_in"))
      (node (ref "U85") (pin "11") (pinfunction "GND2_11") (pintype "power_in"))
      (node (ref "U85") (pin "16") (pinfunction "~{2OE}_16") (pintype "passive"))
    )
    (net (code "57") (name "Net-(U6-1DIR)") (class "Default")
      (node (ref "R35") (pin "1") (pinfunction "1_1") (pintype "passive"))
      (node (ref "U6") (pin "4") (pinfunction "1DIR_4") (pintype "passive"))
    )
    (net (code "58") (name "Net-(U6-2DIR)") (class "Default")
      (node (ref "R31") (pin "2") (pinfunction "2_2") (pintype "passive"))
      (node (ref "U6") (pin "5") (pinfunction "2DIR_5") (pintype "passive"))
    )
    (net (code "59") (name "Net-(U8-~{G})") (class "Default")
      (node (ref "R30") (pin "1") (pinfunction "1_1") (pintype "passive"))
      (node (ref "U8") (pin "7") (pinfunction "~{G}_7") (pintype "passive"))
    )
    (net (code "60") (name "Net-(U12-1DIR)") (class "Default")
      (node (ref "R51") (pin "1") (pinfunction "1_1") (pintype "passive"))
      (node (ref "U12") (pin "4") (pinfunction "1DIR_4") (pintype "passive"))
    )
    (net (code "61") (name "Net-(U12-2DIR)") (class "Default")
      (node (ref "R42") (pin "2") (pinfunction "2_2") (pintype "passive"))
      (node (ref "U12") (pin "5") (pinfunction "2DIR_5") (pintype "passive"))
    )
    (net (code "62") (name "Net-(U19-1DIR)") (class "Default")
      (node (ref "R89") (pin "1") (pinfunction "1_1") (pintype "passive"))
      (node (ref "U19") (pin "4") (pinfunction "1DIR_4") (pintype "passive"))
    )
    (net (code "63") (name "Net-(U19-2DIR)") (class "Default")
      (node (ref "R80") (pin "2") (pinfunction "2_2") (pintype "passive"))
      (node (ref "U19") (pin "5") (pinfunction "2DIR_5") (pintype "passive"))
    )
    (net (code "64") (name "Net-(U21-1DIR)") (class "Default")
      (node (ref "R113") (pin "1") (pinfunction "1_1") (pintype "passive"))
      (node (ref "U21") (pin "4") (pinfunction "1DIR_4") (pintype "passive"))
    )
    (net (code "65") (name "Net-(U21-2DIR)") (class "Default")
      (node (ref "R116") (pin "2") (pinfunction "2_2") (pintype "passive"))
      (node (ref "U21") (pin "5") (pinfunction "2DIR_5") (pintype "passive"))
    )
    (net (code "66") (name "Net-(U23-~{G})") (class "Default")
      (node (ref "R125") (pin "1") (pinfunction "1_1") (pintype "passive"))
      (node (ref "U23") (pin "7") (pinfunction "~{G}_7") (pintype "passive"))
    )
    (net (code "67") (name "Net-(U26-~{E})") (class "Default")
      (node (ref "R176") (pin "1") (pinfunction "1_1") (pintype "passive"))
      (node (ref "U26") (pin "15") (pinfunction "~{E}_15") (pintype "input"))
    )
    (net (code "68") (name "Net-(U65-~{G})") (class "Default")
      (node (ref "R356") (pin "1") (pinfunction "1_1") (pintype "passive"))
      (node (ref "U65") (pin "7") (pinfunction "~{G}_7") (pintype "passive"))
    )
    (net (code "69") (name "Net-(U83-~{G})") (class "Default")
      (node (ref "R440") (pin "1") (pinfunction "1_1") (pintype "passive"))
      (node (ref "U83") (pin "7") (pinfunction "~{G}_7") (pintype "passive"))
    )
    (net (code "70") (name "Net-(U85-1DIR)") (class "Default")
      (node (ref "R447") (pin "1") (pinfunction "1_1") (pintype "passive"))
      (node (ref "U85") (pin "4") (pinfunction "1DIR_4") (pintype "passive"))
    )
    (net (code "71") (name "Net-(U85-2DIR)") (class "Default")
      (node (ref "R452") (pin "2") (pinfunction "2_2") (pintype "passive"))
      (node (ref "U85") (pin "5") (pinfunction "2DIR_5") (pintype "passive"))
    )
    (net (code "72") (name "VCC1V8") (class "Default")
      (node (ref "C16") (pin "1") (pinfunction "1_1") (pintype "passive"))
      (node (ref "C21") (pin "1") (pinfunction "1_1") (pintype "passive"))
      (node (ref "C285") (pin "1") (pinfunction "1_1") (pintype "passive"))
      (node (ref "C396") (pin "1") (pinfunction "1_1") (pintype "passive"))
      (node (ref "C41") (pin "1") (pinfunction "1_1") (pintype "passive"))
      (node (ref "R35") (pin "2") (pinfunction "2_2") (pintype "passive"))
      (node (ref "R447") (pin "2") (pinfunction "2_2") (pintype "passive"))
      (node (ref "R51") (pin "2") (pinfunction "2_2") (pintype "passive"))
      (node (ref "U12") (pin "3") (pinfunction "VCCA_3") (pintype "power_in"))
      (node (ref "U6") (pin "3") (pinfunction "VCCA_3") (pintype "power_in"))
      (node (ref "U65") (pin "8") (pinfunction "VCC_8") (pintype "power_in"))
      (node (ref "U8") (pin "8") (pinfunction "VCC_8") (pintype "power_in"))
      (node (ref "U85") (pin "3") (pinfunction "VCCA_3") (pintype "power_in"))
    )
    (net (code "73") (name "VCC3V3_IO") (class "Default")
      (node (ref "C103") (pin "1") (pinfunction "1_1") (pintype "passive"))
      (node (ref "C119") (pin "1") (pinfunction "1_1") (pintype "passive"))
      (node (ref "C146") (pin "1") (pinfunction "1_1") (pintype "passive"))
      (node (ref "C20") (pin "1") (pinfunction "1_1") (pintype "passive"))
      (node (ref "C379") (pin "1") (pinfunction "1_1") (pintype "passive"))
      (node (ref "C92") (pin "1") (pinfunction "1_1") (pintype "passive"))
      (node (ref "R113") (pin "2") (pinfunction "2_2") (pintype "passive"))
      (node (ref "R120") (pin "1") (pinfunction "1_1") (pintype "passive"))
      (node (ref "R134") (pin "1") (pinfunction "1_1") (pintype "passive"))
      (node (ref "R89") (pin "2") (pinfunction "2_2") (pintype "passive"))
      (node (ref "U19") (pin "3") (pinfunction "VCCA_3") (pintype "power_in"))
      (node (ref "U21") (pin "3") (pinfunction "VCCA_3") (pintype "power_in"))
      (node (ref "U23") (pin "8") (pinfunction "VCC_8") (pintype "power_in"))
      (node (ref "U26") (pin "16") (pinfunction "VCC_16") (pintype "power_in"))
      (node (ref "U6") (pin "2") (pinfunction "VCCB_2") (pintype "power_in"))
      (node (ref "U83") (pin "8") (pinfunction "VCC_8") (pintype "power_in"))
    )
    (net (code "74") (name "VCC_3V3_FT4232") (class "Default")
      (node (ref "C397") (pin "1") (pinfunction "1_1") (pintype "passive"))
      (node (ref "C40") (pin "1") (pinfunction "1_1") (pintype "passive"))
      (node (ref "C91") (pin "1") (pinfunction "1_1") (pintype "passive"))
      (node (ref "C94") (pin "1") (pinfunction "1_1") (pintype "passive"))
      (node (ref "U12") (pin "2") (pinfunction "VCCB_2") (pintype "power_in"))
      (node (ref "U19") (pin "2") (pinfunction "VCCB_2") (pintype "power_in"))
      (node (ref "U21") (pin "2") (pinfunction "VCCB_2") (pintype "power_in"))
      (node (ref "U85") (pin "2") (pinfunction "VCCB_2") (pintype "power_in"))
    )
    (net (code "75") (name "unconnected-(U8-~{Y}-Pad3)") (class "Default")
      (node (ref "U8") (pin "3") (pinfunction "~{Y}_3") (pintype "passive+no_connect"))
    )
    (net (code "76") (name "unconnected-(U23-~{Y}-Pad3)") (class "Default")
      (node (ref "U23") (pin "3") (pinfunction "~{Y}_3") (pintype "passive+no_connect"))
    )
    (net (code "77") (name "unconnected-(U65-~{Y}-Pad3)") (class "Default")
      (node (ref "U65") (pin "3") (pinfunction "~{Y}_3") (pintype "passive+no_connect"))
    )
    (net (code "78") (name "unconnected-(U83-~{Y}-Pad3)") (class "Default")
      (node (ref "U83") (pin "3") (pinfunction "~{Y}_3") (pintype "passive+no_connect"))
    )
  )
)
